# lp_small.net
KiCad netlist of a schematic drawn in EAGLE
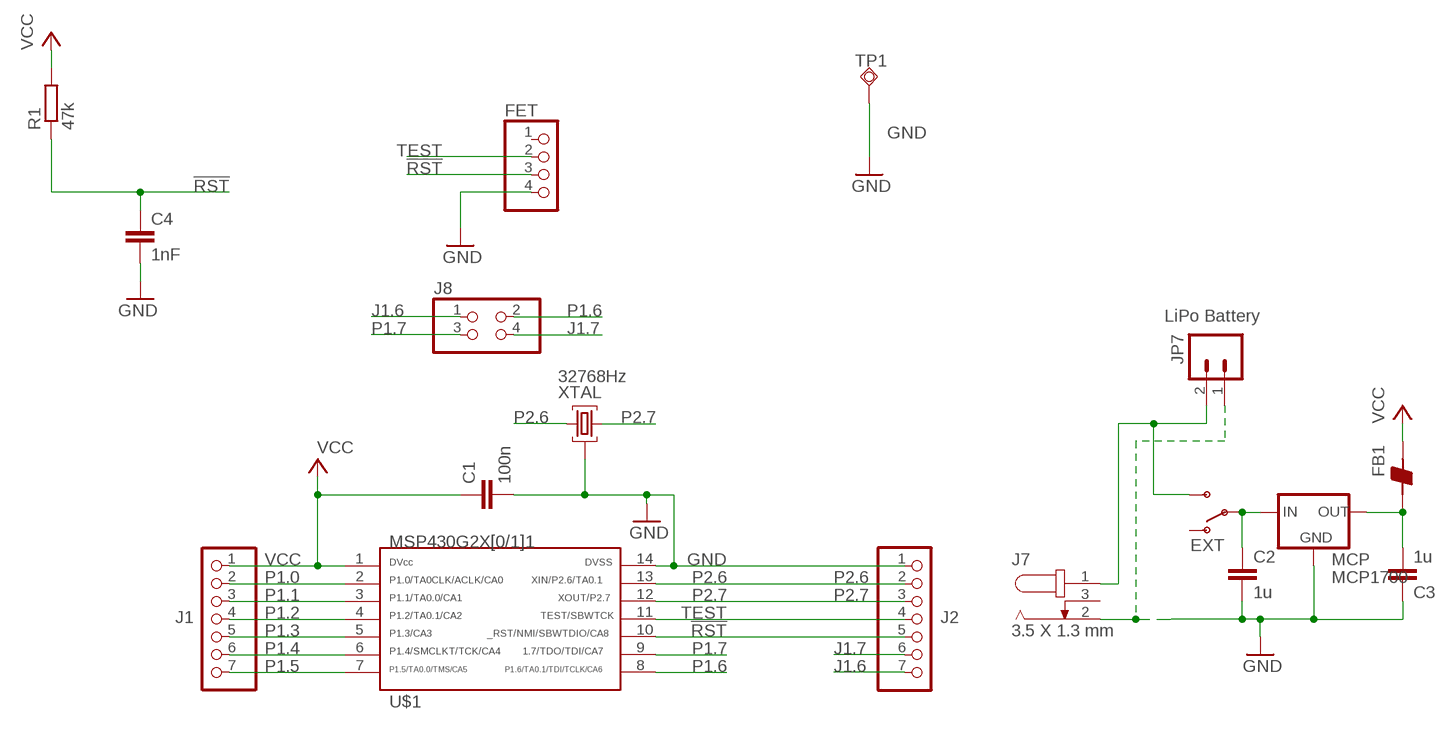
[diagram p0: schematic, sheet 1]

(export (version "E")
  (design (tool "Eeschema 10.0.6"))
  (components
    (comp (ref "C1")
      (value "100n")
      (footprint "eagle-import:C0805")
      (libsource (lib "eagle-import") (part "C-EUC0805"))
    )
    (comp (ref "C2")
      (value "1u")
      (footprint "eagle-import:C0805")
      (libsource (lib "eagle-import") (part "C-EUC0805"))
    )
    (comp (ref "C3")
      (value "1u")
      (footprint "eagle-import:C0805")
      (libsource (lib "eagle-import") (part "C-EUC0805"))
    )
    (comp (ref "C4")
      (value "1nF")
      (footprint "eagle-import:C0805")
      (libsource (lib "eagle-import") (part "resistor_C-EUC0805"))
    )
    (comp (ref "FB1")
      (value "BEAD-0805")
      (footprint "eagle-import:0805")
      (libsource (lib "eagle-import") (part "BEAD-0805"))
    )
    (comp (ref "FET")
      (value "PINHD-1X4")
      (footprint "eagle-import:1X04")
      (libsource (lib "eagle-import") (part "PINHD-1X4"))
    )
    (comp (ref "J1")
      (value "PINHD-1X7")
      (footprint "eagle-import:1X07")
      (libsource (lib "eagle-import") (part "PINHD-1X7"))
    )
    (comp (ref "J2")
      (value "PINHD-1X7")
      (footprint "eagle-import:1X07")
      (libsource (lib "eagle-import") (part "PINHD-1X7"))
    )
    (comp (ref "J7")
      (value "3.5 X 1.3 mm")
      (footprint "eagle-import:3.5X1.3MM_DC_JACK")
      (libsource (lib "eagle-import") (part "DC_JACK_3.5X1.3MM"))
    )
    (comp (ref "J8")
      (value "PINHD-2X2")
      (footprint "eagle-import:2X02")
      (libsource (lib "eagle-import") (part "PINHD-2X2"))
    )
    (comp (ref "JP7")
      (value "LiPo Battery")
      (footprint "eagle-import:JST-2-PTH")
      (libsource (lib "eagle-import") (part "M02JST-PTH-2"))
    )
    (comp (ref "MCP")
      (value "MCP1700")
      (footprint "eagle-import:SOT-23")
      (libsource (lib "eagle-import") (part "MCP1700SOT-23"))
    )
    (comp (ref "ON")
      (value "EXT")
      (footprint "eagle-import:SWITCH-SPDT")
      (libsource (lib "eagle-import") (part "SWITCH-SPSTPTH"))
    )
    (comp (ref "R1")
      (value "47k")
      (footprint "eagle-import:R0805")
      (libsource (lib "eagle-import") (part "R-EU_R0805"))
    )
    (comp (ref "TP1")
      (value "TPSQTP20R")
      (footprint "eagle-import:TP20R")
      (libsource (lib "eagle-import") (part "TPSQTP20R"))
    )
    (comp (ref "U$1")
      (value "G2X[0/1]1---N14")
      (footprint "eagle-import:N14")
      (libsource (lib "eagle-import") (part "G2X[0/1]1---N14"))
    )
    (comp (ref "XTAL")
      (value "32768Hz")
      (footprint "eagle-import:QUARZ5")
      (libsource (lib "eagle-import") (part "QUARZ5"))
    )
  )
  (nets
    (net (code "1") (name "/J1.6") (class "Default")
      (node (ref "J2") (pin "7") (pinfunction "7_7") (pintype "passive"))
      (node (ref "J8") (pin "1") (pinfunction "1_1") (pintype "passive"))
    )
    (net (code "2") (name "/J1.7") (class "Default")
      (node (ref "J2") (pin "6") (pinfunction "6_6") (pintype "passive"))
      (node (ref "J8") (pin "4") (pinfunction "4_4") (pintype "passive"))
    )
    (net (code "3") (name "/P1.0") (class "Default")
      (node (ref "J1") (pin "2") (pinfunction "2_2") (pintype "passive"))
      (node (ref "U$1") (pin "2") (pinfunction "2_2") (pintype "bidirectional"))
    )
    (net (code "4") (name "/P1.1") (class "Default")
      (node (ref "J1") (pin "3") (pinfunction "3_3") (pintype "passive"))
      (node (ref "U$1") (pin "3") (pinfunction "3_3") (pintype "bidirectional"))
    )
    (net (code "5") (name "/P1.2") (class "Default")
      (node (ref "J1") (pin "4") (pinfunction "4_4") (pintype "passive"))
      (node (ref "U$1") (pin "4") (pinfunction "4_4") (pintype "bidirectional"))
    )
    (net (code "6") (name "/P1.3") (class "Default")
      (node (ref "J1") (pin "5") (pinfunction "5_5") (pintype "passive"))
      (node (ref "U$1") (pin "5") (pinfunction "5_5") (pintype "bidirectional"))
    )
    (net (code "7") (name "/P1.4") (class "Default")
      (node (ref "J1") (pin "6") (pinfunction "6_6") (pintype "passive"))
      (node (ref "U$1") (pin "6") (pinfunction "6_6") (pintype "bidirectional"))
    )
    (net (code "8") (name "/P1.5") (class "Default")
      (node (ref "J1") (pin "7") (pinfunction "7_7") (pintype "passive"))
      (node (ref "U$1") (pin "7") (pinfunction "7_7") (pintype "bidirectional"))
    )
    (net (code "9") (name "/P1.6") (class "Default")
      (node (ref "J8") (pin "2") (pinfunction "2_2") (pintype "passive"))
      (node (ref "U$1") (pin "8") (pinfunction "8_8") (pintype "bidirectional"))
    )
    (net (code "10") (name "/P1.7") (class "Default")
      (node (ref "J8") (pin "3") (pinfunction "3_3") (pintype "passive"))
      (node (ref "U$1") (pin "9") (pinfunction "9_9") (pintype "bidirectional"))
    )
    (net (code "11") (name "/P2.6") (class "Default")
      (node (ref "J2") (pin "2") (pinfunction "2_2") (pintype "passive"))
      (node (ref "U$1") (pin "13") (pinfunction "13_13") (pintype "bidirectional"))
      (node (ref "XTAL") (pin "2") (pinfunction "2_2") (pintype "passive"))
    )
    (net (code "12") (name "/P2.7") (class "Default")
      (node (ref "J2") (pin "3") (pinfunction "3_3") (pintype "passive"))
      (node (ref "U$1") (pin "12") (pinfunction "12_12") (pintype "bidirectional"))
      (node (ref "XTAL") (pin "1") (pinfunction "1_1") (pintype "passive"))
    )
    (net (code "13") (name "/TEST") (class "Default")
      (node (ref "FET") (pin "2") (pinfunction "2_2") (pintype "passive"))
      (node (ref "J2") (pin "4") (pinfunction "4_4") (pintype "passive"))
      (node (ref "U$1") (pin "11") (pinfunction "11_11") (pintype "bidirectional"))
    )
    (net (code "14") (name "/~{RST}") (class "Default")
      (node (ref "C4") (pin "1") (pinfunction "1_1") (pintype "passive"))
      (node (ref "FET") (pin "3") (pinfunction "3_3") (pintype "passive"))
      (node (ref "J2") (pin "5") (pinfunction "5_5") (pintype "passive"))
      (node (ref "R1") (pin "1") (pinfunction "1_1") (pintype "passive"))
      (node (ref "U$1") (pin "10") (pinfunction "10_10") (pintype "bidirectional"))
    )
    (net (code "15") (name "GND") (class "Default")
      (node (ref "C1") (pin "2") (pinfunction "2_2") (pintype "passive"))
      (node (ref "C2") (pin "2") (pinfunction "2_2") (pintype "passive"))
      (node (ref "C3") (pin "1") (pinfunction "1_1") (pintype "passive"))
      (node (ref "C4") (pin "2") (pinfunction "2_2") (pintype "passive"))
      (node (ref "FET") (pin "4") (pinfunction "4_4") (pintype "passive"))
      (node (ref "J2") (pin "1") (pinfunction "1_1") (pintype "passive"))
      (node (ref "J7") (pin "2") (pinfunction "2_2") (pintype "passive"))
      (node (ref "JP7") (pin "1") (pinfunction "1_1") (pintype "passive"))
      (node (ref "MCP") (pin "1") (pinfunction "GND_1") (pintype "input"))
      (node (ref "TP1") (pin "TP") (pinfunction "TP_TP") (pintype "input"))
      (node (ref "U$1") (pin "14") (pinfunction "14_14") (pintype "bidirectional"))
      (node (ref "XTAL") (pin "GND@0") (pinfunction "0_GND@0") (pintype "passive"))
    )
    (net (code "16") (name "Net-(FB1-P$1)") (class "Default")
      (node (ref "C3") (pin "2") (pinfunction "2_2") (pintype "passive"))
      (node (ref "FB1") (pin "1") (pinfunction "P$1_1") (pintype "passive"))
      (node (ref "MCP") (pin "2") (pinfunction "OUT_2") (pintype "passive"))
    )
    (net (code "17") (name "Net-(MCP-IN)") (class "Default")
      (node (ref "C2") (pin "1") (pinfunction "1_1") (pintype "passive"))
      (node (ref "MCP") (pin "3") (pinfunction "IN_3") (pintype "input"))
      (node (ref "ON") (pin "2") (pinfunction "P_2") (pintype "passive"))
    )
    (net (code "18") (name "Net-(ON-S)") (class "Default")
      (node (ref "J7") (pin "1") (pinfunction "1_1") (pintype "passive"))
      (node (ref "JP7") (pin "2") (pinfunction "2_2") (pintype "passive"))
      (node (ref "ON") (pin "3") (pinfunction "S_3") (pintype "passive"))
    )
    (net (code "19") (name "VCC") (class "Default")
      (node (ref "C1") (pin "1") (pinfunction "1_1") (pintype "passive"))
      (node (ref "FB1") (pin "2") (pinfunction "P$2_2") (pintype "passive"))
      (node (ref "J1") (pin "1") (pinfunction "1_1") (pintype "passive"))
      (node (ref "R1") (pin "2") (pinfunction "2_2") (pintype "passive"))
      (node (ref "U$1") (pin "1") (pinfunction "1_1") (pintype "bidirectional"))
    )
    (net (code "20") (name "unconnected-(FET-Pad1)") (class "Default")
      (node (ref "FET") (pin "1") (pinfunction "1_1") (pintype "passive"))
    )
    (net (code "21") (name "unconnected-(J7-Pad3)") (class "Default")
      (node (ref "J7") (pin "3") (pinfunction "3_3") (pintype "passive"))
    )
    (net (code "22") (name "unconnected-(ON-O-Pad1)") (class "Default")
      (node (ref "ON") (pin "1") (pinfunction "O_1") (pintype "passive"))
    )
  )
)
